# MAIN.net
KiCad netlist of a schematic drawn in Altium Designer
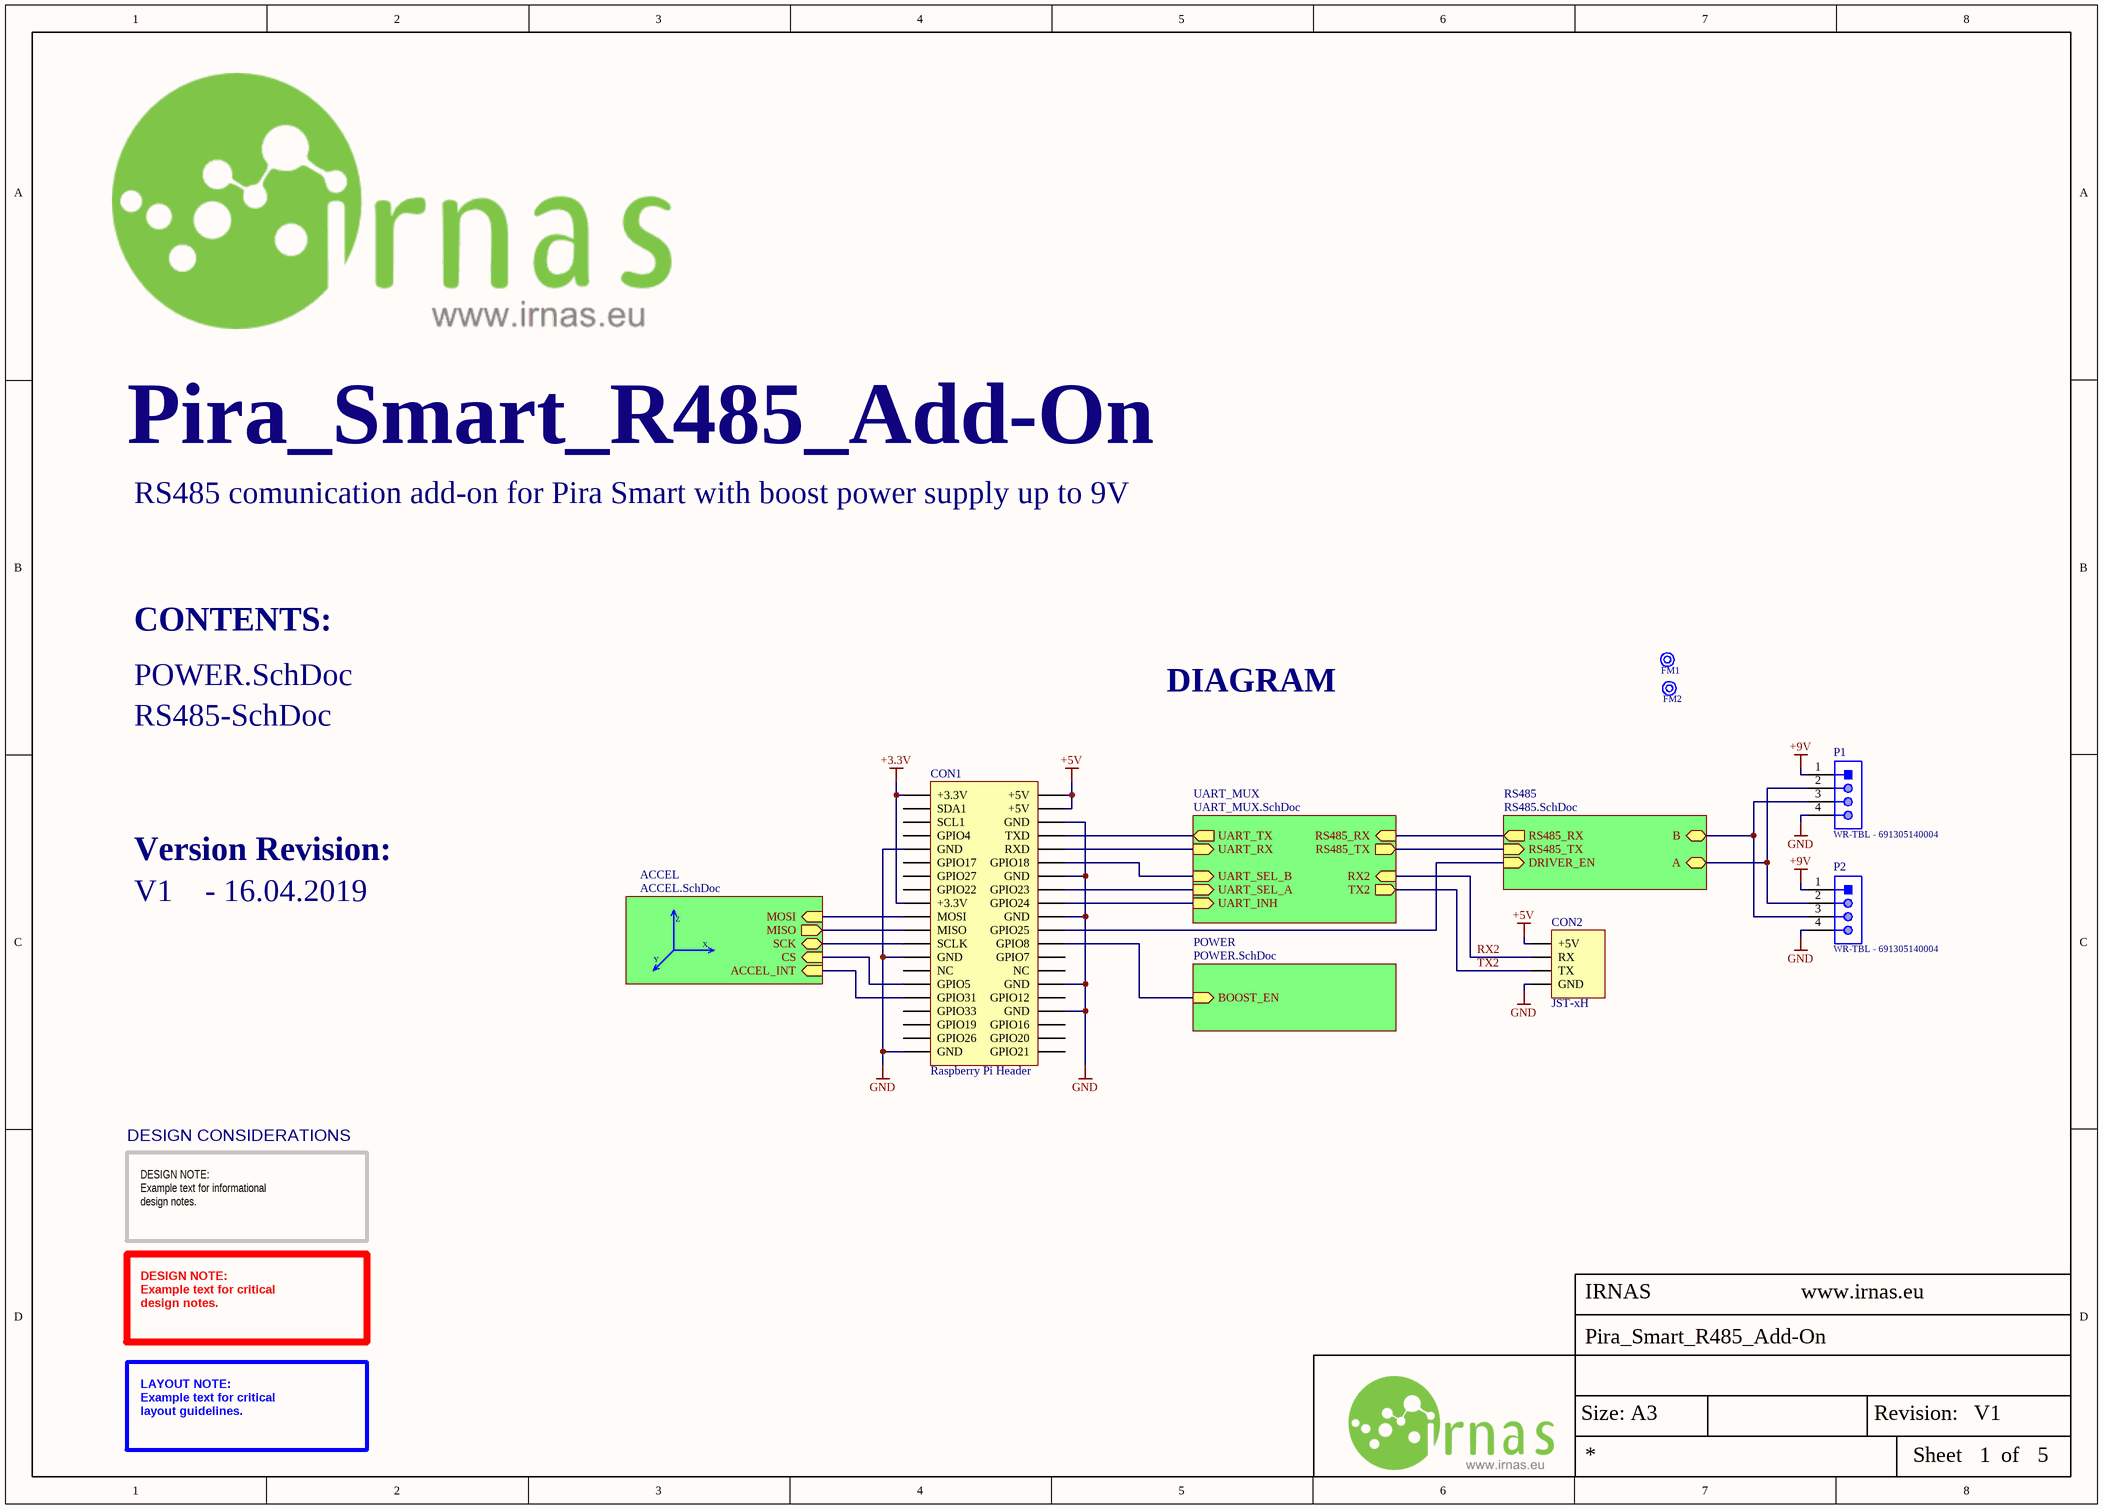
[diagram p0: MAIN.SchDoc]

(export (version "E")
  (design (tool "Eeschema 10.0.6"))
  (components
    (comp (ref "CON1")
      (value "Raspberry Pi Header")
      (footprint "Connectors:HDR2X20")
      (description "Header, 20-Pin, Dual row")
      (fields (field (name "PUBLISHER") "Altium Limited"))
      (libsource (lib "Connectors") (part "Raspberry Pi Header"))
    )
    (comp (ref "CON2")
      (value "JST-xH")
      (footprint "JST-xH")
      (description "4 Positions Header, Shrouded Connector 0.098\" (2.50mm) Through Hole Tin")
      (fields
        (field (name "MANUFACTURER") "JST")
        (field (name "MANUFACTURER PART NUMBER") "B4B-XH-A(LF)(SN)")
      )
      (libsource (lib "Connectors") (part "B4B-XH-A(LF)(SN)"))
    )
    (comp (ref "FM1")
      (value "FIDUCAL MARKER")
      (footprint "Mechanical:FIDUCAL")
      (libsource (lib "Mechanical") (part "FIDUCAL"))
    )
    (comp (ref "FM2")
      (value "FIDUCAL MARKER")
      (footprint "Mechanical:FIDUCAL")
      (libsource (lib "Mechanical") (part "FIDUCAL"))
    )
    (comp (ref "P1")
      (value "WR-TBL - 691305140004")
      (footprint "691305140004")
      (description "Serie 3051 - 3.50mm Horizontal PCB Header with Plastic Latch WR-TBL, 4 pin")
      (fields (field (name "PART NUMBER") "691305140004") (field (name "PUBLISHER") "Wurth Elektronik"))
      (libsource (lib "Connectors") (part "WR-TBL - 691305140004"))
    )
    (comp (ref "P2")
      (value "WR-TBL - 691305140004")
      (footprint "691305140004")
      (description "Serie 3051 - 3.50mm Horizontal PCB Header with Plastic Latch WR-TBL, 4 pin")
      (fields (field (name "PART NUMBER") "691305140004") (field (name "PUBLISHER") "Wurth Elektronik"))
      (libsource (lib "Connectors") (part "WR-TBL - 691305140004"))
    )
  )
  (nets
    (net (code "1") (name "+3.3V") (class "Default")
      (node (ref "CON1") (pin "1") (pinfunction "+3.3V_1") (pintype "passive"))
      (node (ref "CON1") (pin "17") (pinfunction "+3.3V_17") (pintype "passive"))
    )
    (net (code "2") (name "+5V") (class "Default")
      (node (ref "CON1") (pin "2") (pinfunction "+5V_2") (pintype "passive"))
      (node (ref "CON1") (pin "4") (pinfunction "+5V_4") (pintype "passive"))
      (node (ref "CON2") (pin "1") (pinfunction "+5V_1") (pintype "passive"))
    )
    (net (code "3") (name "+9V") (class "Default")
      (node (ref "P1") (pin "1") (pinfunction "1_1") (pintype "passive"))
      (node (ref "P2") (pin "1") (pinfunction "1_1") (pintype "passive"))
    )
    (net (code "4") (name "/A") (class "Default")
      (node (ref "P1") (pin "2") (pinfunction "2_2") (pintype "passive"))
      (node (ref "P2") (pin "2") (pinfunction "2_2") (pintype "passive"))
    )
    (net (code "5") (name "/ACCEL_INT") (class "Default")
      (node (ref "CON1") (pin "31") (pinfunction "GPIO31_31") (pintype "passive"))
    )
    (net (code "6") (name "/B") (class "Default")
      (node (ref "P1") (pin "3") (pinfunction "3_3") (pintype "passive"))
      (node (ref "P2") (pin "3") (pinfunction "3_3") (pintype "passive"))
    )
    (net (code "7") (name "/BOOST_EN") (class "Default")
      (node (ref "CON1") (pin "24") (pinfunction "GPIO8_24") (pintype "passive"))
    )
    (net (code "8") (name "/CS") (class "Default")
      (node (ref "CON1") (pin "29") (pinfunction "GPIO5_29") (pintype "passive"))
    )
    (net (code "9") (name "/DRIVER_EN") (class "Default")
      (node (ref "CON1") (pin "22") (pinfunction "GPIO25_22") (pintype "passive"))
    )
    (net (code "10") (name "/MISO") (class "Default")
      (node (ref "CON1") (pin "21") (pinfunction "MISO_21") (pintype "passive"))
    )
    (net (code "11") (name "/MOSI") (class "Default")
      (node (ref "CON1") (pin "19") (pinfunction "MOSI_19") (pintype "passive"))
    )
    (net (code "14") (name "/RX2") (class "Default")
      (node (ref "CON2") (pin "2") (pinfunction "RX_2") (pintype "passive"))
    )
    (net (code "15") (name "/SCK") (class "Default")
      (node (ref "CON1") (pin "23") (pinfunction "SCLK_23") (pintype "passive"))
    )
    (net (code "16") (name "/TX2") (class "Default")
      (node (ref "CON2") (pin "3") (pinfunction "TX_3") (pintype "passive"))
    )
    (net (code "17") (name "/UART_INH") (class "Default")
      (node (ref "CON1") (pin "18") (pinfunction "GPIO24_18") (pintype "passive"))
    )
    (net (code "18") (name "/UART_RX") (class "Default")
      (node (ref "CON1") (pin "10") (pinfunction "RXD_10") (pintype "passive"))
    )
    (net (code "19") (name "/UART_SEL_A") (class "Default")
      (node (ref "CON1") (pin "16") (pinfunction "GPIO23_16") (pintype "passive"))
    )
    (net (code "20") (name "/UART_SEL_B") (class "Default")
      (node (ref "CON1") (pin "12") (pinfunction "GPIO18_12") (pintype "passive"))
    )
    (net (code "21") (name "/UART_TX") (class "Default")
      (node (ref "CON1") (pin "8") (pinfunction "TXD_8") (pintype "passive"))
    )
    (net (code "22") (name "GND") (class "Default")
      (node (ref "CON1") (pin "14") (pinfunction "GND_14") (pintype "passive"))
      (node (ref "CON1") (pin "20") (pinfunction "GND_20") (pintype "passive"))
      (node (ref "CON1") (pin "25") (pinfunction "GND_25") (pintype "passive"))
      (node (ref "CON1") (pin "30") (pinfunction "GND_30") (pintype "passive"))
      (node (ref "CON1") (pin "34") (pinfunction "GND_34") (pintype "passive"))
      (node (ref "CON1") (pin "39") (pinfunction "GND_39") (pintype "passive"))
      (node (ref "CON1") (pin "6") (pinfunction "GND_6") (pintype "passive"))
      (node (ref "CON1") (pin "9") (pinfunction "GND_9") (pintype "passive"))
      (node (ref "CON2") (pin "4") (pinfunction "GND_4") (pintype "passive"))
      (node (ref "P1") (pin "4") (pinfunction "4_4") (pintype "passive"))
      (node (ref "P2") (pin "4") (pinfunction "4_4") (pintype "passive"))
    )
    (net (code "23") (name "unconnected-(CON1-GPIO4-Pad7)") (class "Default")
      (node (ref "CON1") (pin "7") (pinfunction "GPIO4_7") (pintype "passive"))
    )
    (net (code "24") (name "unconnected-(CON1-GPIO7-Pad26)") (class "Default")
      (node (ref "CON1") (pin "26") (pinfunction "GPIO7_26") (pintype "passive"))
    )
    (net (code "25") (name "unconnected-(CON1-GPIO12-Pad32)") (class "Default")
      (node (ref "CON1") (pin "32") (pinfunction "GPIO12_32") (pintype "passive"))
    )
    (net (code "26") (name "unconnected-(CON1-GPIO16-Pad36)") (class "Default")
      (node (ref "CON1") (pin "36") (pinfunction "GPIO16_36") (pintype "passive"))
    )
    (net (code "27") (name "unconnected-(CON1-GPIO17-Pad11)") (class "Default")
      (node (ref "CON1") (pin "11") (pinfunction "GPIO17_11") (pintype "passive"))
    )
    (net (code "28") (name "unconnected-(CON1-GPIO19-Pad35)") (class "Default")
      (node (ref "CON1") (pin "35") (pinfunction "GPIO19_35") (pintype "passive"))
    )
    (net (code "29") (name "unconnected-(CON1-GPIO20-Pad38)") (class "Default")
      (node (ref "CON1") (pin "38") (pinfunction "GPIO20_38") (pintype "passive"))
    )
    (net (code "30") (name "unconnected-(CON1-GPIO21-Pad40)") (class "Default")
      (node (ref "CON1") (pin "40") (pinfunction "GPIO21_40") (pintype "passive"))
    )
    (net (code "31") (name "unconnected-(CON1-GPIO22-Pad15)") (class "Default")
      (node (ref "CON1") (pin "15") (pinfunction "GPIO22_15") (pintype "passive"))
    )
    (net (code "32") (name "unconnected-(CON1-GPIO26-Pad37)") (class "Default")
      (node (ref "CON1") (pin "37") (pinfunction "GPIO26_37") (pintype "passive"))
    )
    (net (code "33") (name "unconnected-(CON1-GPIO27-Pad13)") (class "Default")
      (node (ref "CON1") (pin "13") (pinfunction "GPIO27_13") (pintype "passive"))
    )
    (net (code "34") (name "unconnected-(CON1-GPIO33-Pad33)") (class "Default")
      (node (ref "CON1") (pin "33") (pinfunction "GPIO33_33") (pintype "passive"))
    )
    (net (code "35") (name "unconnected-(CON1-NC-Pad27)") (class "Default")
      (node (ref "CON1") (pin "27") (pinfunction "NC_27") (pintype "passive"))
    )
    (net (code "36") (name "unconnected-(CON1-NC-Pad28)") (class "Default")
      (node (ref "CON1") (pin "28") (pinfunction "NC_28") (pintype "passive"))
    )
    (net (code "37") (name "unconnected-(CON1-SCL1-Pad5)") (class "Default")
      (node (ref "CON1") (pin "5") (pinfunction "SCL1_5") (pintype "passive"))
    )
    (net (code "38") (name "unconnected-(CON1-SDA1-Pad3)") (class "Default")
      (node (ref "CON1") (pin "3") (pinfunction "SDA1_3") (pintype "passive"))
    )
  )
)
